# CONVEYOR-v3_0.net
KiCad netlist of a schematic drawn in EAGLE
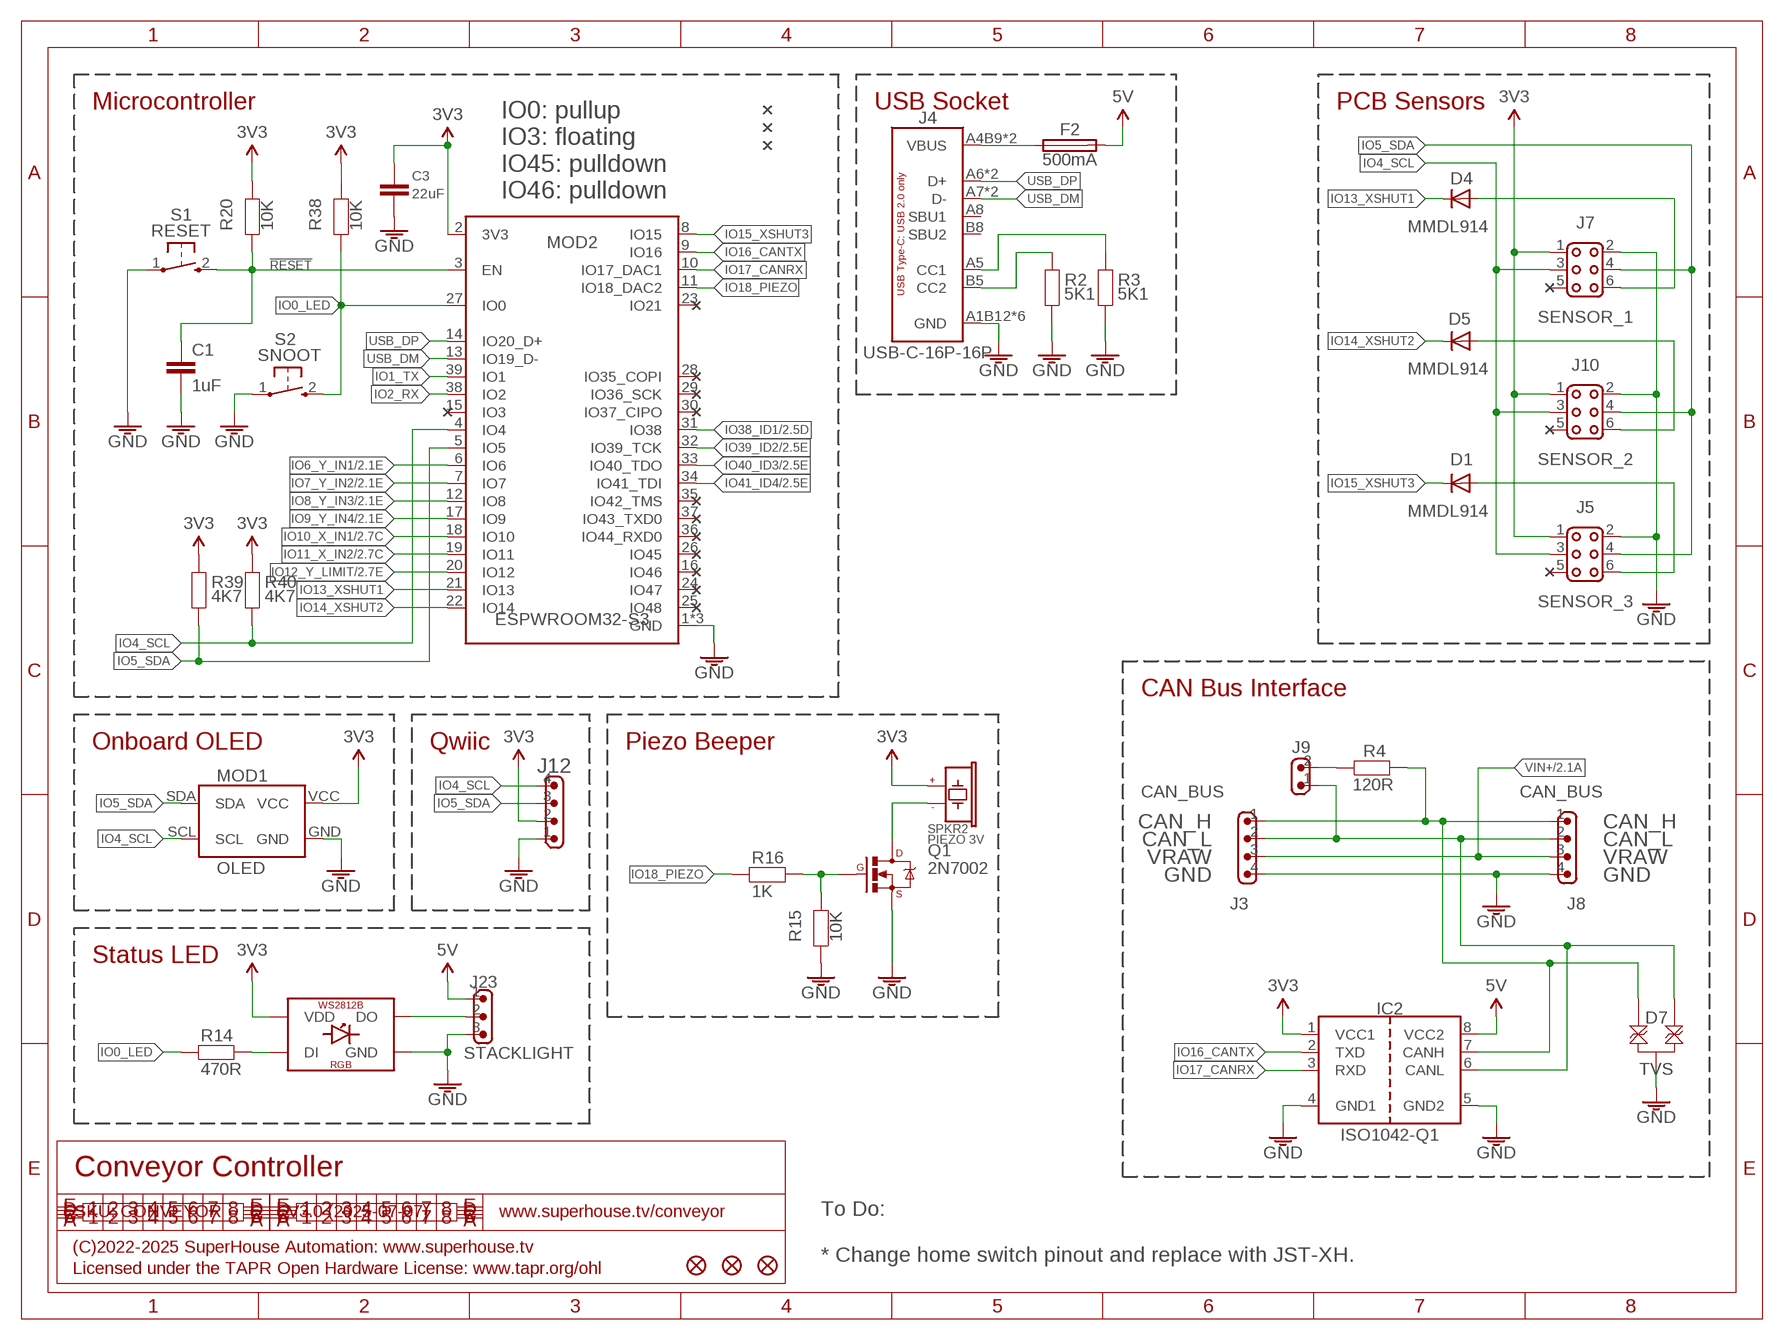
[diagram p0: schematic, sheet 1]
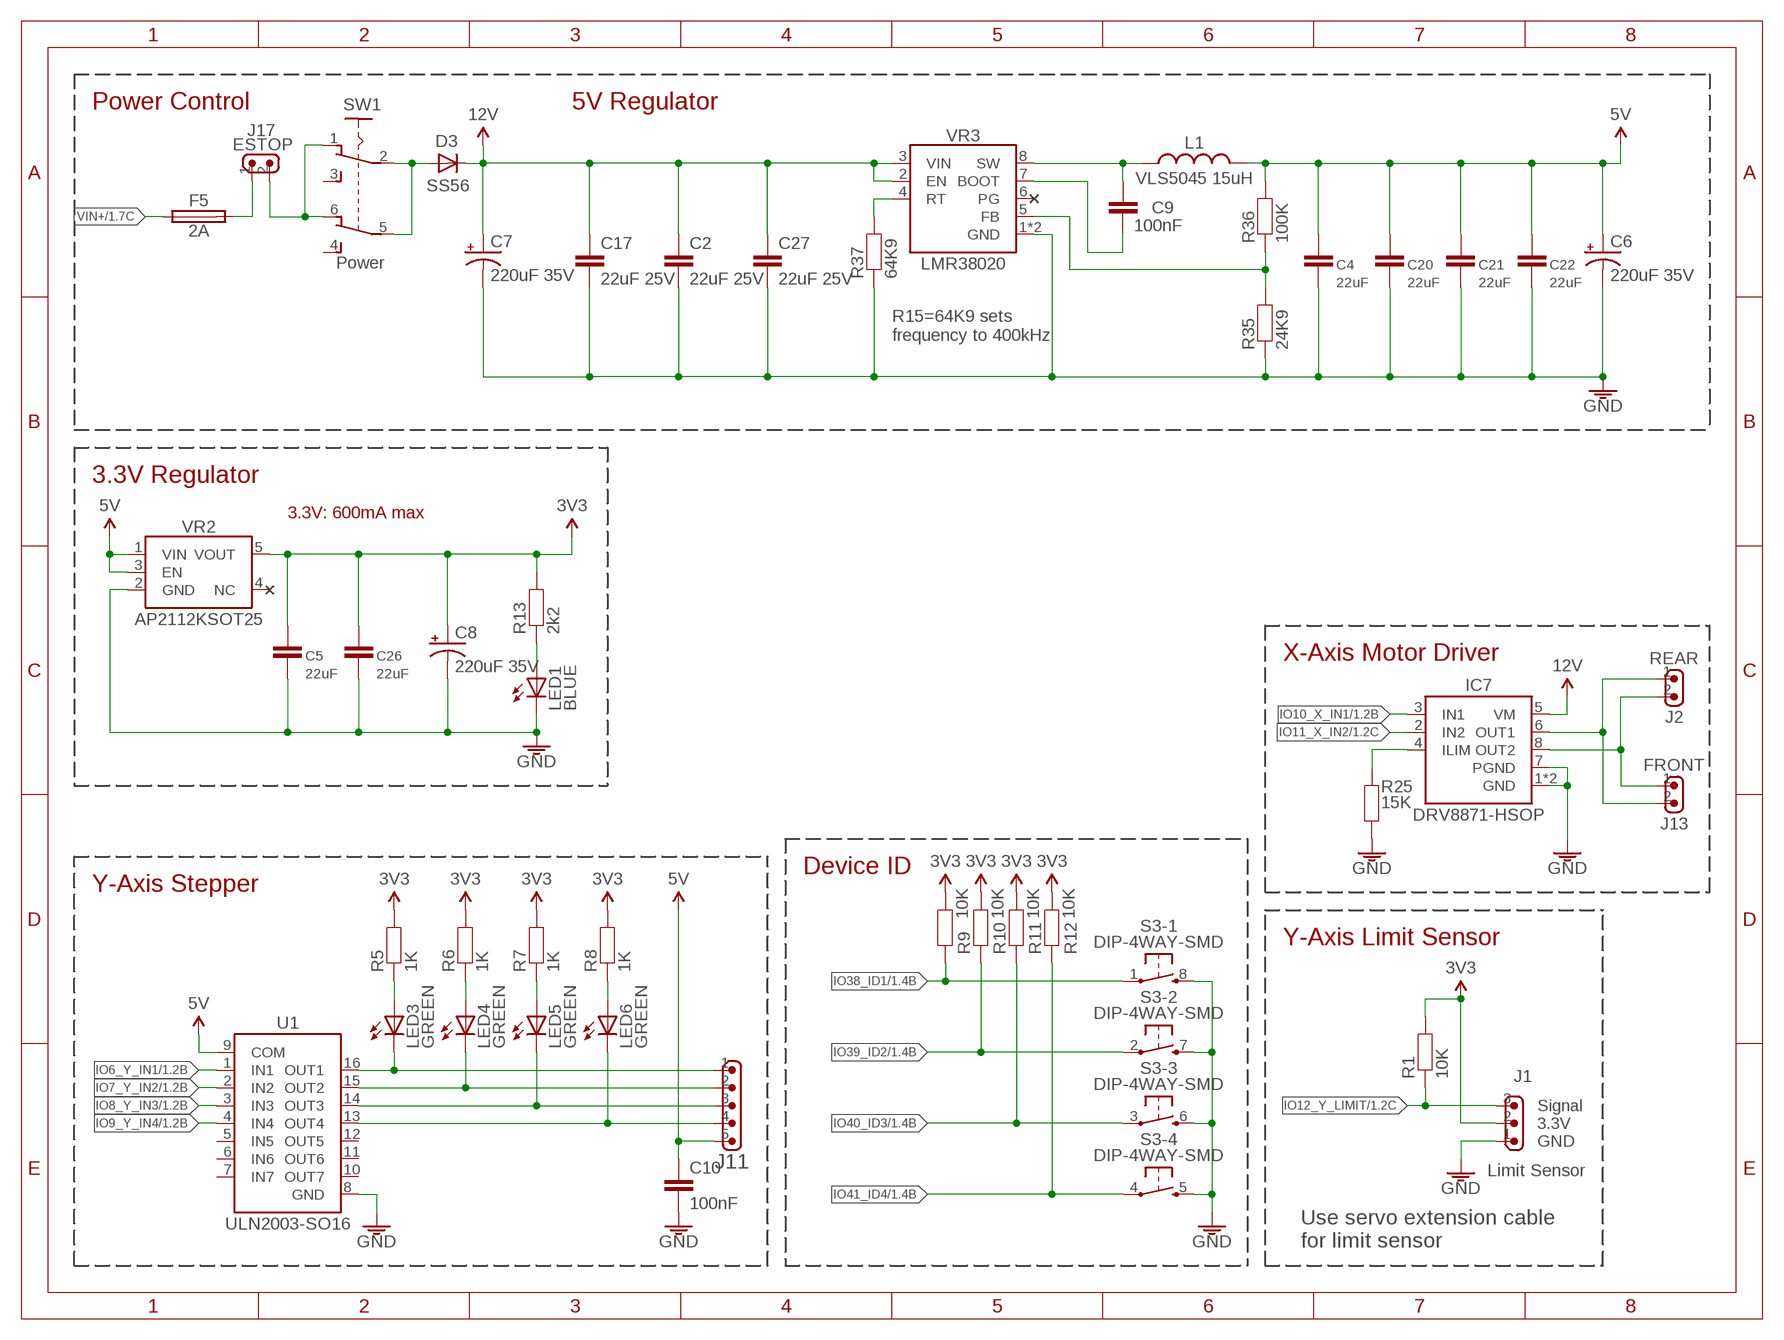
[diagram p1: schematic, sheet 2]

(export (version "E")
  (design (tool "Eeschema 10.0.6"))
  (components
    (comp (ref "C1")
      (value "1uF")
      (footprint "eagle-import:C0603")
      (libsource (lib "eagle-import") (part "CAP0603"))
    )
    (comp (ref "C3")
      (value "22uF")
      (footprint "eagle-import:C0805")
      (libsource (lib "eagle-import") (part "CAP0805"))
    )
    (comp (ref "D1")
      (value "MMDL914")
      (footprint "eagle-import:SOD-123")
      (libsource (lib "eagle-import") (part "SuperHouse-Diodes_vf.Wm7B3QdcQ5eJ3TSsqbKpHg_DIODE-SOD123"))
    )
    (comp (ref "D4")
      (value "MMDL914")
      (footprint "eagle-import:SOD-123")
      (libsource (lib "eagle-import") (part "SuperHouse-Diodes_vf.Wm7B3QdcQ5eJ3TSsqbKpHg_DIODE-SOD123"))
    )
    (comp (ref "D5")
      (value "MMDL914")
      (footprint "eagle-import:SOD-123")
      (libsource (lib "eagle-import") (part "SuperHouse-Diodes_vf.Wm7B3QdcQ5eJ3TSsqbKpHg_DIODE-SOD123"))
    )
    (comp (ref "D7")
      (value "TVS")
      (footprint "eagle-import:SOT23-3")
      (libsource (lib "eagle-import") (part "TVSDUAL-T24CAN"))
    )
    (comp (ref "F2")
      (value "500mA")
      (footprint "eagle-import:1206")
      (libsource (lib "eagle-import") (part "PTC-1206"))
    )
    (comp (ref "IC2")
      (value "ISO1042-Q1")
      (footprint "eagle-import:SO08-W")
      (libsource (lib "eagle-import") (part "ISO1042-Q1"))
    )
    (comp (ref "J3")
      (value "CAN_BUS")
      (footprint "eagle-import:SCREWTERMINAL-3.81MM-PLUGGABLE-HOR-4")
      (libsource (lib "eagle-import") (part "M04-SCREW-3.81MM-HOR-PLUG"))
    )
    (comp (ref "J4")
      (value "USB-C-16P-16P")
      (footprint "eagle-import:USB-C-16P")
      (libsource (lib "eagle-import") (part "USB-C-16P-16P"))
    )
    (comp (ref "J5")
      (value "SENSOR_3")
      (footprint "eagle-import:2X3-2.54-SHROUDED")
      (libsource (lib "eagle-import") (part "M02X3-SHROUDED"))
    )
    (comp (ref "J7")
      (value "SENSOR_1")
      (footprint "eagle-import:2X3-2.54-SHROUDED")
      (libsource (lib "eagle-import") (part "M02X3-SHROUDED"))
    )
    (comp (ref "J8")
      (value "CAN_BUS")
      (footprint "eagle-import:SCREWTERMINAL-3.81MM-PLUGGABLE-HOR-4")
      (libsource (lib "eagle-import") (part "M04-SCREW-3.81MM-HOR-PLUG"))
    )
    (comp (ref "J9")
      (value "M02-PIN-JUMP-Y")
      (footprint "eagle-import:1X02-P-JUMP-Y")
      (libsource (lib "eagle-import") (part "SuperHouse-Connectors_vf.joDh8IkZQLOHsS2h9VhiTg_M02-PIN-JUMP-Y"))
    )
    (comp (ref "J10")
      (value "SENSOR_2")
      (footprint "eagle-import:2X3-2.54-SHROUDED")
      (libsource (lib "eagle-import") (part "M02X3-SHROUDED"))
    )
    (comp (ref "J12")
      (value "M04-SM4B-SH")
      (footprint "eagle-import:JST-SM4B-SH")
      (libsource (lib "eagle-import") (part "M04-SM4B-SH"))
    )
    (comp (ref "J23")
      (value "STACKLIGHT")
      (footprint "eagle-import:1X03")
      (libsource (lib "eagle-import") (part "M03-PLAIN"))
    )
    (comp (ref "LED2")
      (value "WS2812B-PTH5MM")
      (footprint "eagle-import:5MM4PIN")
      (libsource (lib "eagle-import") (part "WS2812B-PTH5MM"))
    )
    (comp (ref "MOD1")
      (value "OLED")
      (footprint "eagle-import:OLED-128X32-0.91-HEADER")
      (libsource (lib "eagle-import") (part "OLED-I2C-128X32-0.91-HEADER"))
    )
    (comp (ref "MOD2")
      (value "ESPWROOM32-S3")
      (footprint "eagle-import:ESPWROOM32-S3")
      (libsource (lib "eagle-import") (part "ESPWROOM32-S3-WROOM"))
    )
    (comp (ref "Q1")
      (value "2N7002")
      (footprint "eagle-import:SOT23-3")
      (libsource (lib "eagle-import") (part "MOSFET-NCHANNEL-233"))
    )
    (comp (ref "R2")
      (value "5K1")
      (footprint "eagle-import:R0603")
      (libsource (lib "eagle-import") (part "RESISTOR0603"))
    )
    (comp (ref "R3")
      (value "5K1")
      (footprint "eagle-import:R0603")
      (libsource (lib "eagle-import") (part "RESISTOR0603"))
    )
    (comp (ref "R4")
      (value "120R")
      (footprint "eagle-import:R2010")
      (libsource (lib "eagle-import") (part "RESISTOR2010"))
    )
    (comp (ref "R14")
      (value "470R")
      (footprint "eagle-import:R0603")
      (libsource (lib "eagle-import") (part "RESISTOR0603"))
    )
    (comp (ref "R15")
      (value "10K")
      (footprint "eagle-import:R0603")
      (libsource (lib "eagle-import") (part "RESISTOR0603"))
    )
    (comp (ref "R16")
      (value "1K")
      (footprint "eagle-import:R0603")
      (libsource (lib "eagle-import") (part "RESISTOR0603"))
    )
    (comp (ref "R20")
      (value "10K")
      (footprint "eagle-import:R0603")
      (libsource (lib "eagle-import") (part "RESISTOR0603"))
    )
    (comp (ref "R38")
      (value "10K")
      (footprint "eagle-import:R0603")
      (libsource (lib "eagle-import") (part "RESISTOR0603"))
    )
    (comp (ref "R39")
      (value "4K7")
      (footprint "eagle-import:R0603")
      (libsource (lib "eagle-import") (part "RESISTOR0603"))
    )
    (comp (ref "R40")
      (value "4K7")
      (footprint "eagle-import:R0603")
      (libsource (lib "eagle-import") (part "RESISTOR0603"))
    )
    (comp (ref "S1")
      (value "RESET")
      (footprint "eagle-import:TACTILE_SMT_3X4X2")
      (libsource (lib "eagle-import") (part "TAC_SWITCH_2PINSMT"))
    )
    (comp (ref "S2")
      (value "SNOOT")
      (footprint "eagle-import:TACTILE_SMT_3X4X2")
      (libsource (lib "eagle-import") (part "TAC_SWITCH_2PINSMT"))
    )
    (comp (ref "SPKR2")
      (value "PIEZO 3V")
      (footprint "eagle-import:PIEZO-9.6X9.6-SMT")
      (libsource (lib "eagle-import") (part "PIEZOPOLARISED-SMT"))
    )
    (comp (ref "U$4")
      (value "FIDUCIAL1X2.5")
      (footprint "eagle-import:FIDUCIAL-1X2.5")
      (libsource (lib "eagle-import") (part "FIDUCIAL1X2.5"))
    )
    (comp (ref "U$5")
      (value "FIDUCIAL1X2.5")
      (footprint "eagle-import:FIDUCIAL-1X2.5")
      (libsource (lib "eagle-import") (part "FIDUCIAL1X2.5"))
    )
    (comp (ref "U$6")
      (value "FIDUCIAL1X2.5")
      (footprint "eagle-import:FIDUCIAL-1X2.5")
      (libsource (lib "eagle-import") (part "FIDUCIAL1X2.5"))
    )
    (comp (ref "C2")
      (value "22uF 25V")
      (footprint "eagle-import:C0805")
      (libsource (lib "eagle-import") (part "CAP0805"))
    )
    (comp (ref "C4")
      (value "22uF")
      (footprint "eagle-import:C0805")
      (libsource (lib "eagle-import") (part "CAP0805"))
    )
    (comp (ref "C5")
      (value "22uF")
      (footprint "eagle-import:C0805")
      (libsource (lib "eagle-import") (part "CAP0805"))
    )
    (comp (ref "C6")
      (value "220uF 35V")
      (footprint "eagle-import:PANASONIC_G")
      (libsource (lib "eagle-import") (part "CAP_POLG"))
    )
    (comp (ref "C7")
      (value "220uF 35V")
      (footprint "eagle-import:PANASONIC_G")
      (libsource (lib "eagle-import") (part "CAP_POLG"))
    )
    (comp (ref "C8")
      (value "220uF 35V")
      (footprint "eagle-import:PANASONIC_G")
      (libsource (lib "eagle-import") (part "CAP_POLG"))
    )
    (comp (ref "C9")
      (value "100nF")
      (footprint "eagle-import:C0603")
      (libsource (lib "eagle-import") (part "CAP0603"))
    )
    (comp (ref "C10")
      (value "100nF")
      (footprint "eagle-import:C0603")
      (libsource (lib "eagle-import") (part "CAP0603"))
    )
    (comp (ref "C17")
      (value "22uF 25V")
      (footprint "eagle-import:C0805")
      (libsource (lib "eagle-import") (part "CAP0805"))
    )
    (comp (ref "C20")
      (value "22uF")
      (footprint "eagle-import:C0805")
      (libsource (lib "eagle-import") (part "CAP0805"))
    )
    (comp (ref "C21")
      (value "22uF")
      (footprint "eagle-import:C0805")
      (libsource (lib "eagle-import") (part "CAP0805"))
    )
    (comp (ref "C22")
      (value "22uF")
      (footprint "eagle-import:C0805")
      (libsource (lib "eagle-import") (part "CAP0805"))
    )
    (comp (ref "C26")
      (value "22uF")
      (footprint "eagle-import:C0805")
      (libsource (lib "eagle-import") (part "CAP0805"))
    )
    (comp (ref "C27")
      (value "22uF 25V")
      (footprint "eagle-import:C0805")
      (libsource (lib "eagle-import") (part "CAP0805"))
    )
    (comp (ref "D3")
      (value "SS56")
      (footprint "eagle-import:SMA-DIODE")
      (libsource (lib "eagle-import") (part "DIODESMA"))
    )
    (comp (ref "F5")
      (value "2A")
      (footprint "eagle-import:OMNIBLOK")
      (libsource (lib "eagle-import") (part "FUSE-OMNIBLOK"))
    )
    (comp (ref "IC7")
      (value "DRV8871-HSOP")
      (footprint "eagle-import:SOIC8T")
      (libsource (lib "eagle-import") (part "DRV8871-HSOP"))
    )
    (comp (ref "J1")
      (value "Limit Sensor")
      (footprint "eagle-import:1X03-P")
      (libsource (lib "eagle-import") (part "M03-PIN"))
    )
    (comp (ref "J2")
      (value "REAR")
      (footprint "eagle-import:JST-B2B-XH-A")
      (libsource (lib "eagle-import") (part "SuperHouse-Connectors_vf.joDh8IkZQLOHsS2h9VhiTg_M02-B2B-XH"))
    )
    (comp (ref "J11")
      (value "M05-B5B-XH")
      (footprint "eagle-import:JST-B5B-XH-A")
      (libsource (lib "eagle-import") (part "M05-B5B-XH"))
    )
    (comp (ref "J13")
      (value "FRONT")
      (footprint "eagle-import:JST-B2B-XH-A")
      (libsource (lib "eagle-import") (part "SuperHouse-Connectors_vf.joDh8IkZQLOHsS2h9VhiTg_M02-B2B-XH"))
    )
    (comp (ref "J17")
      (value "ESTOP")
      (footprint "eagle-import:SCREWTERMINAL-3.81MM-PLUGGABLE-HOR-2")
      (libsource (lib "eagle-import") (part "M02-SCREW-3.81MM-HOR"))
    )
    (comp (ref "L1")
      (value "VLS5045 15uH")
      (footprint "eagle-import:INDUCTOR-5045")
      (libsource (lib "eagle-import") (part "INDUCTOR-5045"))
    )
    (comp (ref "LED1")
      (value "BLUE")
      (footprint "eagle-import:LED-0603")
      (libsource (lib "eagle-import") (part "LED0603"))
    )
    (comp (ref "LED3")
      (value "GREEN")
      (footprint "eagle-import:LED-0603")
      (libsource (lib "eagle-import") (part "LED0603"))
    )
    (comp (ref "LED4")
      (value "GREEN")
      (footprint "eagle-import:LED-0603")
      (libsource (lib "eagle-import") (part "LED0603"))
    )
    (comp (ref "LED5")
      (value "GREEN")
      (footprint "eagle-import:LED-0603")
      (libsource (lib "eagle-import") (part "LED0603"))
    )
    (comp (ref "LED6")
      (value "GREEN")
      (footprint "eagle-import:LED-0603")
      (libsource (lib "eagle-import") (part "LED0603"))
    )
    (comp (ref "R1")
      (value "10K")
      (footprint "eagle-import:R0603")
      (libsource (lib "eagle-import") (part "RESISTOR0603"))
    )
    (comp (ref "R5")
      (value "1K")
      (footprint "eagle-import:R0603")
      (libsource (lib "eagle-import") (part "RESISTOR0603"))
    )
    (comp (ref "R6")
      (value "1K")
      (footprint "eagle-import:R0603")
      (libsource (lib "eagle-import") (part "RESISTOR0603"))
    )
    (comp (ref "R7")
      (value "1K")
      (footprint "eagle-import:R0603")
      (libsource (lib "eagle-import") (part "RESISTOR0603"))
    )
    (comp (ref "R8")
      (value "1K")
      (footprint "eagle-import:R0603")
      (libsource (lib "eagle-import") (part "RESISTOR0603"))
    )
    (comp (ref "R9")
      (value "10K")
      (footprint "eagle-import:R0603")
      (libsource (lib "eagle-import") (part "RESISTOR0603"))
    )
    (comp (ref "R10")
      (value "10K")
      (footprint "eagle-import:R0603")
      (libsource (lib "eagle-import") (part "RESISTOR0603"))
    )
    (comp (ref "R11")
      (value "10K")
      (footprint "eagle-import:R0603")
      (libsource (lib "eagle-import") (part "RESISTOR0603"))
    )
    (comp (ref "R12")
      (value "10K")
      (footprint "eagle-import:R0603")
      (libsource (lib "eagle-import") (part "RESISTOR0603"))
    )
    (comp (ref "R13")
      (value "2k2")
      (footprint "eagle-import:R0603")
      (libsource (lib "eagle-import") (part "RESISTOR0603"))
    )
    (comp (ref "R25")
      (value "15K")
      (footprint "eagle-import:R0603")
      (libsource (lib "eagle-import") (part "RESISTOR0603"))
    )
    (comp (ref "R35")
      (value "24K9")
      (footprint "eagle-import:R0603")
      (libsource (lib "eagle-import") (part "RESISTOR0603"))
    )
    (comp (ref "R36")
      (value "100K")
      (footprint "eagle-import:R0603")
      (libsource (lib "eagle-import") (part "RESISTOR0603"))
    )
    (comp (ref "R37")
      (value "64K9")
      (footprint "eagle-import:R0603")
      (libsource (lib "eagle-import") (part "RESISTOR0603"))
    )
    (comp (ref "S3")
      (value "DIP-4WAY-SMD")
      (footprint "eagle-import:DIP-8-SMD")
      (libsource (lib "eagle-import") (part "DIP-4WAY-SMD"))
    )
    (comp (ref "SW1")
      (value "Power")
      (footprint "eagle-import:7201SD9AV2BE")
      (libsource (lib "eagle-import") (part "SWITCH-DPDT3"))
    )
    (comp (ref "U1")
      (value "ULN2003-SO16")
      (footprint "eagle-import:SO16")
      (libsource (lib "eagle-import") (part "ULN2003-SO16"))
    )
    (comp (ref "VR2")
      (value "AP2112KSOT25")
      (footprint "eagle-import:SOT23-5")
      (libsource (lib "eagle-import") (part "AP2112KSOT25"))
    )
    (comp (ref "VR3")
      (value "LMR38020")
      (footprint "eagle-import:HSOIC8")
      (libsource (lib "eagle-import") (part "LMR38010"))
    )
  )
  (nets
    (net (code "1") (name "3.3V") (class "Default")
      (node (ref "C26") (pin "1") (pinfunction "1_1") (pintype "passive"))
      (node (ref "C3") (pin "1") (pinfunction "1_1") (pintype "passive"))
      (node (ref "C5") (pin "1") (pinfunction "1_1") (pintype "passive"))
      (node (ref "C8") (pin "+") (pinfunction "+_+") (pintype "passive"))
      (node (ref "IC2") (pin "1") (pinfunction "VCC1_1") (pintype "bidirectional"))
      (node (ref "J1") (pin "2") (pinfunction "2_2") (pintype "passive"))
      (node (ref "J10") (pin "1") (pinfunction "1_1") (pintype "passive"))
      (node (ref "J12") (pin "2") (pinfunction "2_2") (pintype "passive"))
      (node (ref "J5") (pin "1") (pinfunction "1_1") (pintype "passive"))
      (node (ref "J7") (pin "1") (pinfunction "1_1") (pintype "passive"))
      (node (ref "LED2") (pin "2") (pinfunction "VDD_2") (pintype "power_in"))
      (node (ref "MOD1") (pin "VCC") (pinfunction "VCC_VCC") (pintype "bidirectional"))
      (node (ref "MOD2") (pin "2") (pinfunction "3V3_2") (pintype "power_in"))
      (node (ref "R1") (pin "2") (pinfunction "2_2") (pintype "passive"))
      (node (ref "R10") (pin "2") (pinfunction "2_2") (pintype "passive"))
      (node (ref "R11") (pin "2") (pinfunction "2_2") (pintype "passive"))
      (node (ref "R12") (pin "2") (pinfunction "2_2") (pintype "passive"))
      (node (ref "R13") (pin "2") (pinfunction "2_2") (pintype "passive"))
      (node (ref "R20") (pin "1") (pinfunction "1_1") (pintype "passive"))
      (node (ref "R38") (pin "1") (pinfunction "1_1") (pintype "passive"))
      (node (ref "R39") (pin "1") (pinfunction "1_1") (pintype "passive"))
      (node (ref "R40") (pin "1") (pinfunction "1_1") (pintype "passive"))
      (node (ref "R5") (pin "2") (pinfunction "2_2") (pintype "passive"))
      (node (ref "R6") (pin "2") (pinfunction "2_2") (pintype "passive"))
      (node (ref "R7") (pin "2") (pinfunction "2_2") (pintype "passive"))
      (node (ref "R8") (pin "2") (pinfunction "2_2") (pintype "passive"))
      (node (ref "R9") (pin "2") (pinfunction "2_2") (pintype "passive"))
      (node (ref "SPKR2") (pin "1") (pinfunction "+_1") (pintype "bidirectional"))
      (node (ref "VR2") (pin "5") (pinfunction "VOUT_5") (pintype "bidirectional"))
    )
    (net (code "2") (name "5V") (class "Default")
      (node (ref "C10") (pin "1") (pinfunction "1_1") (pintype "passive"))
      (node (ref "C20") (pin "1") (pinfunction "1_1") (pintype "passive"))
      (node (ref "C21") (pin "1") (pinfunction "1_1") (pintype "passive"))
      (node (ref "C22") (pin "1") (pinfunction "1_1") (pintype "passive"))
      (node (ref "C4") (pin "1") (pinfunction "1_1") (pintype "passive"))
      (node (ref "C6") (pin "+") (pinfunction "+_+") (pintype "passive"))
      (node (ref "F2") (pin "2") (pinfunction "2_2") (pintype "passive"))
      (node (ref "IC2") (pin "8") (pinfunction "VCC2_8") (pintype "bidirectional"))
      (node (ref "J11") (pin "5") (pinfunction "5_5") (pintype "passive"))
      (node (ref "J23") (pin "1") (pinfunction "1_1") (pintype "passive"))
      (node (ref "L1") (pin "2") (pinfunction "2_2") (pintype "passive"))
      (node (ref "R36") (pin "2") (pinfunction "2_2") (pintype "passive"))
      (node (ref "U1") (pin "9") (pinfunction "COM_9") (pintype "passive"))
      (node (ref "VR2") (pin "1") (pinfunction "VIN_1") (pintype "bidirectional"))
      (node (ref "VR2") (pin "3") (pinfunction "EN_3") (pintype "bidirectional"))
    )
    (net (code "3") (name "12V") (class "Default")
      (node (ref "C17") (pin "1") (pinfunction "1_1") (pintype "passive"))
      (node (ref "C2") (pin "1") (pinfunction "1_1") (pintype "passive"))
      (node (ref "C27") (pin "1") (pinfunction "1_1") (pintype "passive"))
      (node (ref "C7") (pin "+") (pinfunction "+_+") (pintype "passive"))
      (node (ref "D3") (pin "C") (pinfunction "C_C") (pintype "passive"))
      (node (ref "IC7") (pin "5") (pinfunction "VM_5") (pintype "passive"))
      (node (ref "VR3") (pin "2") (pinfunction "EN_2") (pintype "power_in"))
      (node (ref "VR3") (pin "3") (pinfunction "VIN_3") (pintype "power_in"))
    )
    (net (code "4") (name "GND") (class "Default")
      (node (ref "C1") (pin "2") (pinfunction "2_2") (pintype "passive"))
      (node (ref "C10") (pin "2") (pinfunction "2_2") (pintype "passive"))
      (node (ref "C17") (pin "2") (pinfunction "2_2") (pintype "passive"))
      (node (ref "C2") (pin "2") (pinfunction "2_2") (pintype "passive"))
      (node (ref "C20") (pin "2") (pinfunction "2_2") (pintype "passive"))
      (node (ref "C21") (pin "2") (pinfunction "2_2") (pintype "passive"))
      (node (ref "C22") (pin "2") (pinfunction "2_2") (pintype "passive"))
      (node (ref "C26") (pin "2") (pinfunction "2_2") (pintype "passive"))
      (node (ref "C27") (pin "2") (pinfunction "2_2") (pintype "passive"))
      (node (ref "C3") (pin "2") (pinfunction "2_2") (pintype "passive"))
      (node (ref "C4") (pin "2") (pinfunction "2_2") (pintype "passive"))
      (node (ref "C5") (pin "2") (pinfunction "2_2") (pintype "passive"))
      (node (ref "C6") (pin "-") (pinfunction "-_-") (pintype "passive"))
      (node (ref "C7") (pin "-") (pinfunction "-_-") (pintype "passive"))
      (node (ref "C8") (pin "-") (pinfunction "-_-") (pintype "passive"))
      (node (ref "D7") (pin "3") (pinfunction "3_3") (pintype "passive"))
      (node (ref "IC2") (pin "4") (pinfunction "GND1_4") (pintype "bidirectional"))
      (node (ref "IC2") (pin "5") (pinfunction "GND2_5") (pintype "bidirectional"))
      (node (ref "IC7") (pin "1") (pinfunction "GND_1") (pintype "power_in"))
      (node (ref "IC7") (pin "7") (pinfunction "PGND_7") (pintype "power_in"))
      (node (ref "IC7") (pin "TGND") (pinfunction "GND_TGND") (pintype "power_in"))
      (node (ref "J1") (pin "1") (pinfunction "1_1") (pintype "passive"))
      (node (ref "J10") (pin "2") (pinfunction "2_2") (pintype "passive"))
      (node (ref "J12") (pin "1") (pinfunction "1_1") (pintype "passive"))
      (node (ref "J23") (pin "3") (pinfunction "3_3") (pintype "passive"))
      (node (ref "J3") (pin "4") (pinfunction "4_4") (pintype "passive"))
      (node (ref "J4") (pin "A12B1") (pinfunction "GND_A12B1") (pintype "power_in"))
      (node (ref "J4") (pin "A1B12") (pinfunction "GND_A1B12") (pintype "power_in"))
      (node (ref "J4") (pin "FIX1") (pinfunction "GND_FIX1") (pintype "power_in"))
      (node (ref "J4") (pin "FIX2") (pinfunction "GND_FIX2") (pintype "power_in"))
      (node (ref "J4") (pin "FIX3") (pinfunction "GND_FIX3") (pintype "power_in"))
      (node (ref "J4") (pin "FIX4") (pinfunction "GND_FIX4") (pintype "power_in"))
      (node (ref "J5") (pin "2") (pinfunction "2_2") (pintype "passive"))
      (node (ref "J7") (pin "2") (pinfunction "2_2") (pintype "passive"))
      (node (ref "J8") (pin "4") (pinfunction "4_4") (pintype "passive"))
      (node (ref "LED1") (pin "C") (pinfunction "C_C") (pintype "passive"))
      (node (ref "LED2") (pin "3") (pinfunction "GND_3") (pintype "power_in"))
      (node (ref "MOD1") (pin "GND") (pinfunction "GND_GND") (pintype "bidirectional"))
      (node (ref "MOD2") (pin "1") (pinfunction "GND_1") (pintype "power_in"))
      (node (ref "MOD2") (pin "40") (pinfunction "GND_40") (pintype "power_in"))
      (node (ref "MOD2") (pin "41") (pinfunction "GND_41") (pintype "power_in"))
      (node (ref "Q1") (pin "2") (pinfunction "S_2") (pintype "passive"))
      (node (ref "R15") (pin "2") (pinfunction "2_2") (pintype "passive"))
      (node (ref "R2") (pin "2") (pinfunction "2_2") (pintype "passive"))
      (node (ref "R25") (pin "1") (pinfunction "1_1") (pintype "passive"))
      (node (ref "R3") (pin "2") (pinfunction "2_2") (pintype "passive"))
      (node (ref "R35") (pin "1") (pinfunction "1_1") (pintype "passive"))
      (node (ref "R37") (pin "1") (pinfunction "1_1") (pintype "passive"))
      (node (ref "S1") (pin "1") (pinfunction "P_1") (pintype "passive"))
      (node (ref "S2") (pin "1") (pinfunction "P_1") (pintype "passive"))
      (node (ref "S3") (pin "5") (pinfunction "S_5") (pintype "passive"))
      (node (ref "S3") (pin "6") (pinfunction "S_6") (pintype "passive"))
      (node (ref "S3") (pin "7") (pinfunction "S_7") (pintype "passive"))
      (node (ref "S3") (pin "8") (pinfunction "S_8") (pintype "passive"))
      (node (ref "U1") (pin "8") (pinfunction "GND_8") (pintype "passive"))
      (node (ref "VR2") (pin "2") (pinfunction "GND_2") (pintype "bidirectional"))
      (node (ref "VR3") (pin "1") (pinfunction "GND_1") (pintype "bidirectional"))
      (node (ref "VR3") (pin "TGND") (pinfunction "GND_TGND") (pintype "bidirectional"))
    )
    (net (code "5") (name "IO0_LED") (class "Default")
      (node (ref "MOD2") (pin "27") (pinfunction "IO0_27") (pintype "bidirectional"))
      (node (ref "R14") (pin "1") (pinfunction "1_1") (pintype "passive"))
      (node (ref "R38") (pin "2") (pinfunction "2_2") (pintype "passive"))
      (node (ref "S2") (pin "2") (pinfunction "S_2") (pintype "passive"))
    )
    (net (code "6") (name "IO1_TX") (class "Default")
      (node (ref "MOD2") (pin "39") (pinfunction "IO1_39") (pintype "bidirectional"))
    )
    (net (code "7") (name "IO2_RX") (class "Default")
      (node (ref "MOD2") (pin "38") (pinfunction "IO2_38") (pintype "bidirectional"))
    )
    (net (code "8") (name "IO4_SCL") (class "Default")
      (node (ref "J10") (pin "3") (pinfunction "3_3") (pintype "passive"))
      (node (ref "J12") (pin "4") (pinfunction "4_4") (pintype "passive"))
      (node (ref "J5") (pin "3") (pinfunction "3_3") (pintype "passive"))
      (node (ref "J7") (pin "3") (pinfunction "3_3") (pintype "passive"))
      (node (ref "MOD1") (pin "SCL") (pinfunction "SCL_SCL") (pintype "bidirectional"))
      (node (ref "MOD2") (pin "4") (pinfunction "IO4_4") (pintype "bidirectional"))
      (node (ref "R40") (pin "2") (pinfunction "2_2") (pintype "passive"))
    )
    (net (code "9") (name "IO5_SDA") (class "Default")
      (node (ref "J10") (pin "4") (pinfunction "4_4") (pintype "passive"))
      (node (ref "J12") (pin "3") (pinfunction "3_3") (pintype "passive"))
      (node (ref "J5") (pin "4") (pinfunction "4_4") (pintype "passive"))
      (node (ref "J7") (pin "4") (pinfunction "4_4") (pintype "passive"))
      (node (ref "MOD1") (pin "SDA") (pinfunction "SDA_SDA") (pintype "bidirectional"))
      (node (ref "MOD2") (pin "5") (pinfunction "IO5_5") (pintype "bidirectional"))
      (node (ref "R39") (pin "2") (pinfunction "2_2") (pintype "passive"))
    )
    (net (code "10") (name "IO6_Y_IN1") (class "Default")
      (node (ref "MOD2") (pin "6") (pinfunction "IO6_6") (pintype "bidirectional"))
      (node (ref "U1") (pin "1") (pinfunction "IN1_1") (pintype "passive"))
    )
    (net (code "11") (name "IO7_Y_IN2") (class "Default")
      (node (ref "MOD2") (pin "7") (pinfunction "IO7_7") (pintype "bidirectional"))
      (node (ref "U1") (pin "2") (pinfunction "IN2_2") (pintype "passive"))
    )
    (net (code "12") (name "IO8_Y_IN3") (class "Default")
      (node (ref "MOD2") (pin "12") (pinfunction "IO8_12") (pintype "bidirectional"))
      (node (ref "U1") (pin "3") (pinfunction "IN3_3") (pintype "passive"))
    )
    (net (code "13") (name "IO9_Y_IN4") (class "Default")
      (node (ref "MOD2") (pin "17") (pinfunction "IO9_17") (pintype "bidirectional"))
      (node (ref "U1") (pin "4") (pinfunction "IN4_4") (pintype "passive"))
    )
    (net (code "14") (name "IO10_X_IN1") (class "Default")
      (node (ref "IC7") (pin "3") (pinfunction "IN1_3") (pintype "input"))
      (node (ref "MOD2") (pin "18") (pinfunction "IO10_18") (pintype "bidirectional"))
    )
    (net (code "15") (name "IO11_X_IN2") (class "Default")
      (node (ref "IC7") (pin "2") (pinfunction "IN2_2") (pintype "input"))
      (node (ref "MOD2") (pin "19") (pinfunction "IO11_19") (pintype "bidirectional"))
    )
    (net (code "16") (name "IO12_Y_LIMIT") (class "Default")
      (node (ref "J1") (pin "3") (pinfunction "3_3") (pintype "passive"))
      (node (ref "MOD2") (pin "20") (pinfunction "IO12_20") (pintype "bidirectional"))
      (node (ref "R1") (pin "1") (pinfunction "1_1") (pintype "passive"))
    )
    (net (code "17") (name "IO13_XSHUT1") (class "Default")
      (node (ref "D4") (pin "1") (pinfunction "C_1") (pintype "passive"))
      (node (ref "MOD2") (pin "21") (pinfunction "IO13_21") (pintype "bidirectional"))
    )
    (net (code "18") (name "IO14_XSHUT2") (class "Default")
      (node (ref "D5") (pin "1") (pinfunction "C_1") (pintype "passive"))
      (node (ref "MOD2") (pin "22") (pinfunction "IO14_22") (pintype "bidirectional"))
    )
    (net (code "19") (name "IO15_XSHUT3") (class "Default")
      (node (ref "D1") (pin "1") (pinfunction "C_1") (pintype "passive"))
      (node (ref "MOD2") (pin "8") (pinfunction "IO15_8") (pintype "bidirectional"))
    )
    (net (code "20") (name "IO16_CANTX") (class "Default")
      (node (ref "IC2") (pin "2") (pinfunction "TXD_2") (pintype "bidirectional"))
      (node (ref "MOD2") (pin "9") (pinfunction "IO16_9") (pintype "bidirectional"))
    )
    (net (code "21") (name "IO17_CANRX") (class "Default")
      (node (ref "IC2") (pin "3") (pinfunction "RXD_3") (pintype "bidirectional"))
      (node (ref "MOD2") (pin "10") (pinfunction "IO17_DAC1_10") (pintype "bidirectional"))
    )
    (net (code "22") (name "IO18_PIEZO") (class "Default")
      (node (ref "MOD2") (pin "11") (pinfunction "IO18_DAC2_11") (pintype "bidirectional"))
      (node (ref "R16") (pin "1") (pinfunction "1_1") (pintype "passive"))
    )
    (net (code "23") (name "IO38_ID1") (class "Default")
      (node (ref "MOD2") (pin "31") (pinfunction "IO38_31") (pintype "bidirectional"))
      (node (ref "R9") (pin "1") (pinfunction "1_1") (pintype "passive"))
      (node (ref "S3") (pin "1") (pinfunction "P_1") (pintype "passive"))
    )
    (net (code "24") (name "IO39_ID2") (class "Default")
      (node (ref "MOD2") (pin "32") (pinfunction "IO39_TCK_32") (pintype "bidirectional"))
      (node (ref "R10") (pin "1") (pinfunction "1_1") (pintype "passive"))
      (node (ref "S3") (pin "2") (pinfunction "P_2") (pintype "passive"))
    )
    (net (code "25") (name "IO40_ID3") (class "Default")
      (node (ref "MOD2") (pin "33") (pinfunction "IO40_TDO_33") (pintype "bidirectional"))
      (node (ref "R11") (pin "1") (pinfunction "1_1") (pintype "passive"))
      (node (ref "S3") (pin "3") (pinfunction "P_3") (pintype "passive"))
    )
    (net (code "26") (name "IO41_ID4") (class "Default")
      (node (ref "MOD2") (pin "34") (pinfunction "IO41_TDI_34") (pintype "bidirectional"))
      (node (ref "R12") (pin "1") (pinfunction "1_1") (pintype "passive"))
      (node (ref "S3") (pin "4") (pinfunction "P_4") (pintype "passive"))
    )
    (net (code "27") (name "IO46") (class "Default")
      (node (ref "MOD2") (pin "16") (pinfunction "IO46_16") (pintype "power_in"))
    )
    (net (code "28") (name "Net-(D1-A)") (class "Default")
      (node (ref "D1") (pin "2") (pinfunction "A_2") (pintype "passive"))
      (node (ref "J5") (pin "6") (pinfunction "6_6") (pintype "passive"))
    )
    (net (code "29") (name "Net-(D3-PadA)") (class "Default")
      (node (ref "D3") (pin "A") (pinfunction "A_A") (pintype "passive"))
      (node (ref "SW1") (pin "2") (pinfunction "2_2") (pintype "passive"))
      (node (ref "SW1") (pin "5") (pinfunction "5_5") (pintype "passive"))
    )
    (net (code "30") (name "Net-(D4-A)") (class "Default")
      (node (ref "D4") (pin "2") (pinfunction "A_2") (pintype "passive"))
      (node (ref "J7") (pin "6") (pinfunction "6_6") (pintype "passive"))
    )
    (net (code "31") (name "Net-(D5-A)") (class "Default")
      (node (ref "D5") (pin "2") (pinfunction "A_2") (pintype "passive"))
      (node (ref "J10") (pin "6") (pinfunction "6_6") (pintype "passive"))
    )
    (net (code "32") (name "Net-(F2-Pad1)") (class "Default")
      (node (ref "F2") (pin "1") (pinfunction "1_1") (pintype "passive"))
      (node (ref "J4") (pin "A4B9") (pinfunction "VBUS_A4B9") (pintype "power_in"))
      (node (ref "J4") (pin "A9B4") (pinfunction "VBUS_A9B4") (pintype "power_in"))
    )
    (net (code "33") (name "Net-(F5-Pad2)") (class "Default")
      (node (ref "F5") (pin "2") (pinfunction "2_2") (pintype "passive"))
      (node (ref "J17") (pin "1") (pinfunction "1_1") (pintype "passive"))
    )
    (net (code "34") (name "Net-(IC2-CANH)") (class "Default")
      (node (ref "D7") (pin "2") (pinfunction "2_2") (pintype "passive"))
      (node (ref "IC2") (pin "7") (pinfunction "CANH_7") (pintype "bidirectional"))
      (node (ref "J3") (pin "1") (pinfunction "1_1") (pintype "passive"))
      (node (ref "J8") (pin "1") (pinfunction "1_1") (pintype "passive"))
      (node (ref "R4") (pin "2") (pinfunction "2_2") (pintype "passive"))
    )
    (net (code "35") (name "Net-(IC2-CANL)") (class "Default")
      (node (ref "D7") (pin "1") (pinfunction "1_1") (pintype "passive"))
      (node (ref "IC2") (pin "6") (pinfunction "CANL_6") (pintype "bidirectional"))
      (node (ref "J3") (pin "2") (pinfunction "2_2") (pintype "passive"))
      (node (ref "J8") (pin "2") (pinfunction "2_2") (pintype "passive"))
      (node (ref "J9") (pin "1") (pinfunction "1_1") (pintype "passive"))
    )
    (net (code "36") (name "Net-(IC7-ILIM)") (class "Default")
      (node (ref "IC7") (pin "4") (pinfunction "ILIM_4") (pintype "bidirectional"))
      (node (ref "R25") (pin "2") (pinfunction "2_2") (pintype "passive"))
    )
    (net (code "37") (name "Net-(IC7-OUT1)") (class "Default")
      (node (ref "IC7") (pin "6") (pinfunction "OUT1_6") (pintype "output"))
      (node (ref "J13") (pin "2") (pinfunction "2_2") (pintype "passive"))
      (node (ref "J2") (pin "1") (pinfunction "1_1") (pintype "passive"))
    )
    (net (code "38") (name "Net-(IC7-OUT2)") (class "Default")
      (node (ref "IC7") (pin "8") (pinfunction "OUT2_8") (pintype "output"))
      (node (ref "J13") (pin "1") (pinfunction "1_1") (pintype "passive"))
      (node (ref "J2") (pin "2") (pinfunction "2_2") (pintype "passive"))
    )
    (net (code "39") (name "Net-(J4-CC1)") (class "Default")
      (node (ref "J4") (pin "A5") (pinfunction "CC1_A5") (pintype "bidirectional"))
      (node (ref "R3") (pin "1") (pinfunction "1_1") (pintype "passive"))
    )
    (net (code "40") (name "Net-(J4-CC2)") (class "Default")
      (node (ref "J4") (pin "B5") (pinfunction "CC2_B5") (pintype "bidirectional"))
      (node (ref "R2") (pin "1") (pinfunction "1_1") (pintype "passive"))
    )
    (net (code "41") (name "Net-(J9-Pad2)") (class "Default")
      (node (ref "J9") (pin "2") (pinfunction "2_2") (pintype "passive"))
      (node (ref "R4") (pin "1") (pinfunction "1_1") (pintype "passive"))
    )
    (net (code "42") (name "Net-(J17-Pad2)") (class "Default")
      (node (ref "J17") (pin "2") (pinfunction "2_2") (pintype "passive"))
      (node (ref "SW1") (pin "1") (pinfunction "1_1") (pintype "passive"))
      (node (ref "SW1") (pin "6") (pinfunction "6_6") (pintype "passive"))
    )
    (net (code "43") (name "Net-(LED1-PadA)") (class "Default")
      (node (ref "LED1") (pin "A") (pinfunction "A_A") (pintype "passive"))
      (node (ref "R13") (pin "1") (pinfunction "1_1") (pintype "passive"))
    )
    (net (code "44") (name "Net-(LED2-DI)") (class "Default")
      (node (ref "LED2") (pin "4") (pinfunction "DI_4") (pintype "input"))
      (node (ref "R14") (pin "2") (pinfunction "2_2") (pintype "passive"))
    )
    (net (code "45") (name "Net-(LED2-DO)") (class "Default")
      (node (ref "J23") (pin "2") (pinfunction "2_2") (pintype "passive"))
      (node (ref "LED2") (pin "1") (pinfunction "DO_1") (pintype "output"))
    )
    (net (code "46") (name "Net-(LED3-PadA)") (class "Default")
      (node (ref "LED3") (pin "A") (pinfunction "A_A") (pintype "passive"))
      (node (ref "R5") (pin "1") (pinfunction "1_1") (pintype "passive"))
    )
    (net (code "47") (name "Net-(LED4-PadA)") (class "Default")
      (node (ref "LED4") (pin "A") (pinfunction "A_A") (pintype "passive"))
      (node (ref "R6") (pin "1") (pinfunction "1_1") (pintype "passive"))
    )
    (net (code "48") (name "Net-(LED5-PadA)") (class "Default")
      (node (ref "LED5") (pin "A") (pinfunction "A_A") (pintype "passive"))
      (node (ref "R7") (pin "1") (pinfunction "1_1") (pintype "passive"))
    )
    (net (code "49") (name "Net-(LED6-PadA)") (class "Default")
      (node (ref "LED6") (pin "A") (pinfunction "A_A") (pintype "passive"))
      (node (ref "R8") (pin "1") (pinfunction "1_1") (pintype "passive"))
    )
    (net (code "50") (name "Net-(Q1-D)") (class "Default")
      (node (ref "Q1") (pin "3") (pinfunction "D_3") (pintype "passive"))
      (node (ref "SPKR2") (pin "2") (pinfunction "-_2") (pintype "bidirectional"))
    )
    (net (code "51") (name "Net-(Q1-G)") (class "Default")
      (node (ref "Q1") (pin "1") (pinfunction "G_1") (pintype "passive"))
      (node (ref "R15") (pin "1") (pinfunction "1_1") (pintype "passive"))
      (node (ref "R16") (pin "2") (pinfunction "2_2") (pintype "passive"))
    )
    (net (code "52") (name "Net-(U1-OUT1)") (class "Default")
      (node (ref "J11") (pin "1") (pinfunction "1_1") (pintype "passive"))
      (node (ref "LED3") (pin "C") (pinfunction "C_C") (pintype "passive"))
      (node (ref "U1") (pin "16") (pinfunction "OUT1_16") (pintype "passive"))
    )
    (net (code "53") (name "Net-(U1-OUT2)") (class "Default")
      (node (ref "J11") (pin "2") (pinfunction "2_2") (pintype "passive"))
      (node (ref "LED4") (pin "C") (pinfunction "C_C") (pintype "passive"))
      (node (ref "U1") (pin "15") (pinfunction "OUT2_15") (pintype "passive"))
    )
    (net (code "54") (name "Net-(U1-OUT3)") (class "Default")
      (node (ref "J11") (pin "3") (pinfunction "3_3") (pintype "passive"))
      (node (ref "LED5") (pin "C") (pinfunction "C_C") (pintype "passive"))
      (node (ref "U1") (pin "14") (pinfunction "OUT3_14") (pintype "passive"))
    )
    (net (code "55") (name "Net-(U1-OUT4)") (class "Default")
      (node (ref "J11") (pin "4") (pinfunction "4_4") (pintype "passive"))
      (node (ref "LED6") (pin "C") (pinfunction "C_C") (pintype "passive"))
      (node (ref "U1") (pin "13") (pinfunction "OUT4_13") (pintype "passive"))
    )
    (net (code "56") (name "Net-(VR3-BOOT)") (class "Default")
      (node (ref "C9") (pin "2") (pinfunction "2_2") (pintype "passive"))
      (node (ref "VR3") (pin "7") (pinfunction "BOOT_7") (pintype "bidirectional"))
    )
    (net (code "57") (name "Net-(VR3-FB)") (class "Default")
      (node (ref "R35") (pin "2") (pinfunction "2_2") (pintype "passive"))
      (node (ref "R36") (pin "1") (pinfunction "1_1") (pintype "passive"))
      (node (ref "VR3") (pin "5") (pinfunction "FB_5") (pintype "power_in"))
    )
    (net (code "58") (name "Net-(VR3-RT)") (class "Default")
      (node (ref "R37") (pin "2") (pinfunction "2_2") (pintype "passive"))
      (node (ref "VR3") (pin "4") (pinfunction "RT_4") (pintype "power_in"))
    )
    (net (code "59") (name "Net-(VR3-SW)") (class "Default")
      (node (ref "C9") (pin "1") (pinfunction "1_1") (pintype "passive"))
      (node (ref "L1") (pin "1") (pinfunction "1_1") (pintype "passive"))
      (node (ref "VR3") (pin "8") (pinfunction "SW_8") (pintype "bidirectional"))
    )
    (net (code "60") (name "PG") (class "Default")
      (node (ref "VR3") (pin "6") (pinfunction "PG_6") (pintype "power_in"))
    )
    (net (code "61") (name "USB_DM") (class "Default")
      (node (ref "J4") (pin "A7") (pinfunction "D-_A7") (pintype "bidirectional"))
      (node (ref "J4") (pin "B7") (pinfunction "D-_B7") (pintype "bidirectional"))
      (node (ref "MOD2") (pin "13") (pinfunction "IO19_D-_13") (pintype "bidirectional"))
    )
    (net (code "62") (name "USB_DP") (class "Default")
      (node (ref "J4") (pin "A6") (pinfunction "D+_A6") (pintype "bidirectional"))
      (node (ref "J4") (pin "B6") (pinfunction "D+_B6") (pintype "bidirectional"))
      (node (ref "MOD2") (pin "14") (pinfunction "IO20_D+_14") (pintype "bidirectional"))
    )
    (net (code "63") (name "VIN+") (class "Default")
      (node (ref "F5") (pin "1") (pinfunction "1_1") (pintype "passive"))
      (node (ref "J3") (pin "3") (pinfunction "3_3") (pintype "passive"))
      (node (ref "J8") (pin "3") (pinfunction "3_3") (pintype "passive"))
    )
    (net (code "64") (name "unconnected-(J4-SBU1-PadA8)") (class "Default")
      (node (ref "J4") (pin "A8") (pinfunction "SBU1_A8") (pintype "bidirectional"))
    )
    (net (code "65") (name "unconnected-(J4-SBU2-PadB8)") (class "Default")
      (node (ref "J4") (pin "B8") (pinfunction "SBU2_B8") (pintype "bidirectional"))
    )
    (net (code "66") (name "unconnected-(J5-Pad5)") (class "Default")
      (node (ref "J5") (pin "5") (pinfunction "5_5") (pintype "passive"))
    )
    (net (code "67") (name "unconnected-(J7-Pad5)") (class "Default")
      (node (ref "J7") (pin "5") (pinfunction "5_5") (pintype "passive"))
    )
    (net (code "68") (name "unconnected-(J10-Pad5)") (class "Default")
      (node (ref "J10") (pin "5") (pinfunction "5_5") (pintype "passive"))
    )
    (net (code "69") (name "unconnected-(MOD2-IO3-Pad15)") (class "Default")
      (node (ref "MOD2") (pin "15") (pinfunction "IO3_15") (pintype "bidirectional"))
    )
    (net (code "70") (name "unconnected-(MOD2-IO21-Pad23)") (class "Default")
      (node (ref "MOD2") (pin "23") (pinfunction "IO21_23") (pintype "bidirectional"))
    )
    (net (code "71") (name "unconnected-(MOD2-IO35_COPI-Pad28)") (class "Default")
      (node (ref "MOD2") (pin "28") (pinfunction "IO35_COPI_28") (pintype "bidirectional"))
    )
    (net (code "72") (name "unconnected-(MOD2-IO36_SCK-Pad29)") (class "Default")
      (node (ref "MOD2") (pin "29") (pinfunction "IO36_SCK_29") (pintype "bidirectional"))
    )
    (net (code "73") (name "unconnected-(MOD2-IO37_CIPO-Pad30)") (class "Default")
      (node (ref "MOD2") (pin "30") (pinfunction "IO37_CIPO_30") (pintype "bidirectional"))
    )
    (net (code "74") (name "unconnected-(MOD2-IO42_TMS-Pad35)") (class "Default")
      (node (ref "MOD2") (pin "35") (pinfunction "IO42_TMS_35") (pintype "bidirectional"))
    )
    (net (code "75") (name "unconnected-(MOD2-IO43_TXD0-Pad37)") (class "Default")
      (node (ref "MOD2") (pin "37") (pinfunction "IO43_TXD0_37") (pintype "bidirectional"))
    )
    (net (code "76") (name "unconnected-(MOD2-IO44_RXD0-Pad36)") (class "Default")
      (node (ref "MOD2") (pin "36") (pinfunction "IO44_RXD0_36") (pintype "bidirectional"))
    )
    (net (code "77") (name "unconnected-(MOD2-IO45-Pad26)") (class "Default")
      (node (ref "MOD2") (pin "26") (pinfunction "IO45_26") (pintype "bidirectional"))
    )
    (net (code "78") (name "unconnected-(MOD2-IO47-Pad24)") (class "Default")
      (node (ref "MOD2") (pin "24") (pinfunction "IO47_24") (pintype "bidirectional"))
    )
    (net (code "79") (name "unconnected-(MOD2-IO48-Pad25)") (class "Default")
      (node (ref "MOD2") (pin "25") (pinfunction "IO48_25") (pintype "bidirectional"))
    )
    (net (code "80") (name "unconnected-(SW1-Pad3)") (class "Default")
      (node (ref "SW1") (pin "3") (pinfunction "3_3") (pintype "passive"))
    )
    (net (code "81") (name "unconnected-(SW1-Pad4)") (class "Default")
      (node (ref "SW1") (pin "4") (pinfunction "4_4") (pintype "passive"))
    )
    (net (code "82") (name "unconnected-(U1-IN5-Pad5)") (class "Default")
      (node (ref "U1") (pin "5") (pinfunction "IN5_5") (pintype "passive"))
    )
    (net (code "83") (name "unconnected-(U1-IN6-Pad6)") (class "Default")
      (node (ref "U1") (pin "6") (pinfunction "IN6_6") (pintype "passive"))
    )
    (net (code "84") (name "unconnected-(U1-IN7-Pad7)") (class "Default")
      (node (ref "U1") (pin "7") (pinfunction "IN7_7") (pintype "passive"))
    )
    (net (code "85") (name "unconnected-(U1-OUT5-Pad12)") (class "Default")
      (node (ref "U1") (pin "12") (pinfunction "OUT5_12") (pintype "passive"))
    )
    (net (code "86") (name "unconnected-(U1-OUT6-Pad11)") (class "Default")
      (node (ref "U1") (pin "11") (pinfunction "OUT6_11") (pintype "passive"))
    )
    (net (code "87") (name "unconnected-(U1-OUT7-Pad10)") (class "Default")
      (node (ref "U1") (pin "10") (pinfunction "OUT7_10") (pintype "passive"))
    )
    (net (code "88") (name "unconnected-(VR2-NC-Pad4)") (class "Default")
      (node (ref "VR2") (pin "4") (pinfunction "NC_4") (pintype "bidirectional"))
    )
    (net (code "89") (name "~{RESET}") (class "Default")
      (node (ref "C1") (pin "1") (pinfunction "1_1") (pintype "passive"))
      (node (ref "MOD2") (pin "3") (pinfunction "EN_3") (pintype "bidirectional"))
      (node (ref "R20") (pin "2") (pinfunction "2_2") (pintype "passive"))
      (node (ref "S1") (pin "2") (pinfunction "S_2") (pintype "passive"))
    )
  )
)
